# Round.net
KiCad netlist of a schematic drawn in EAGLE
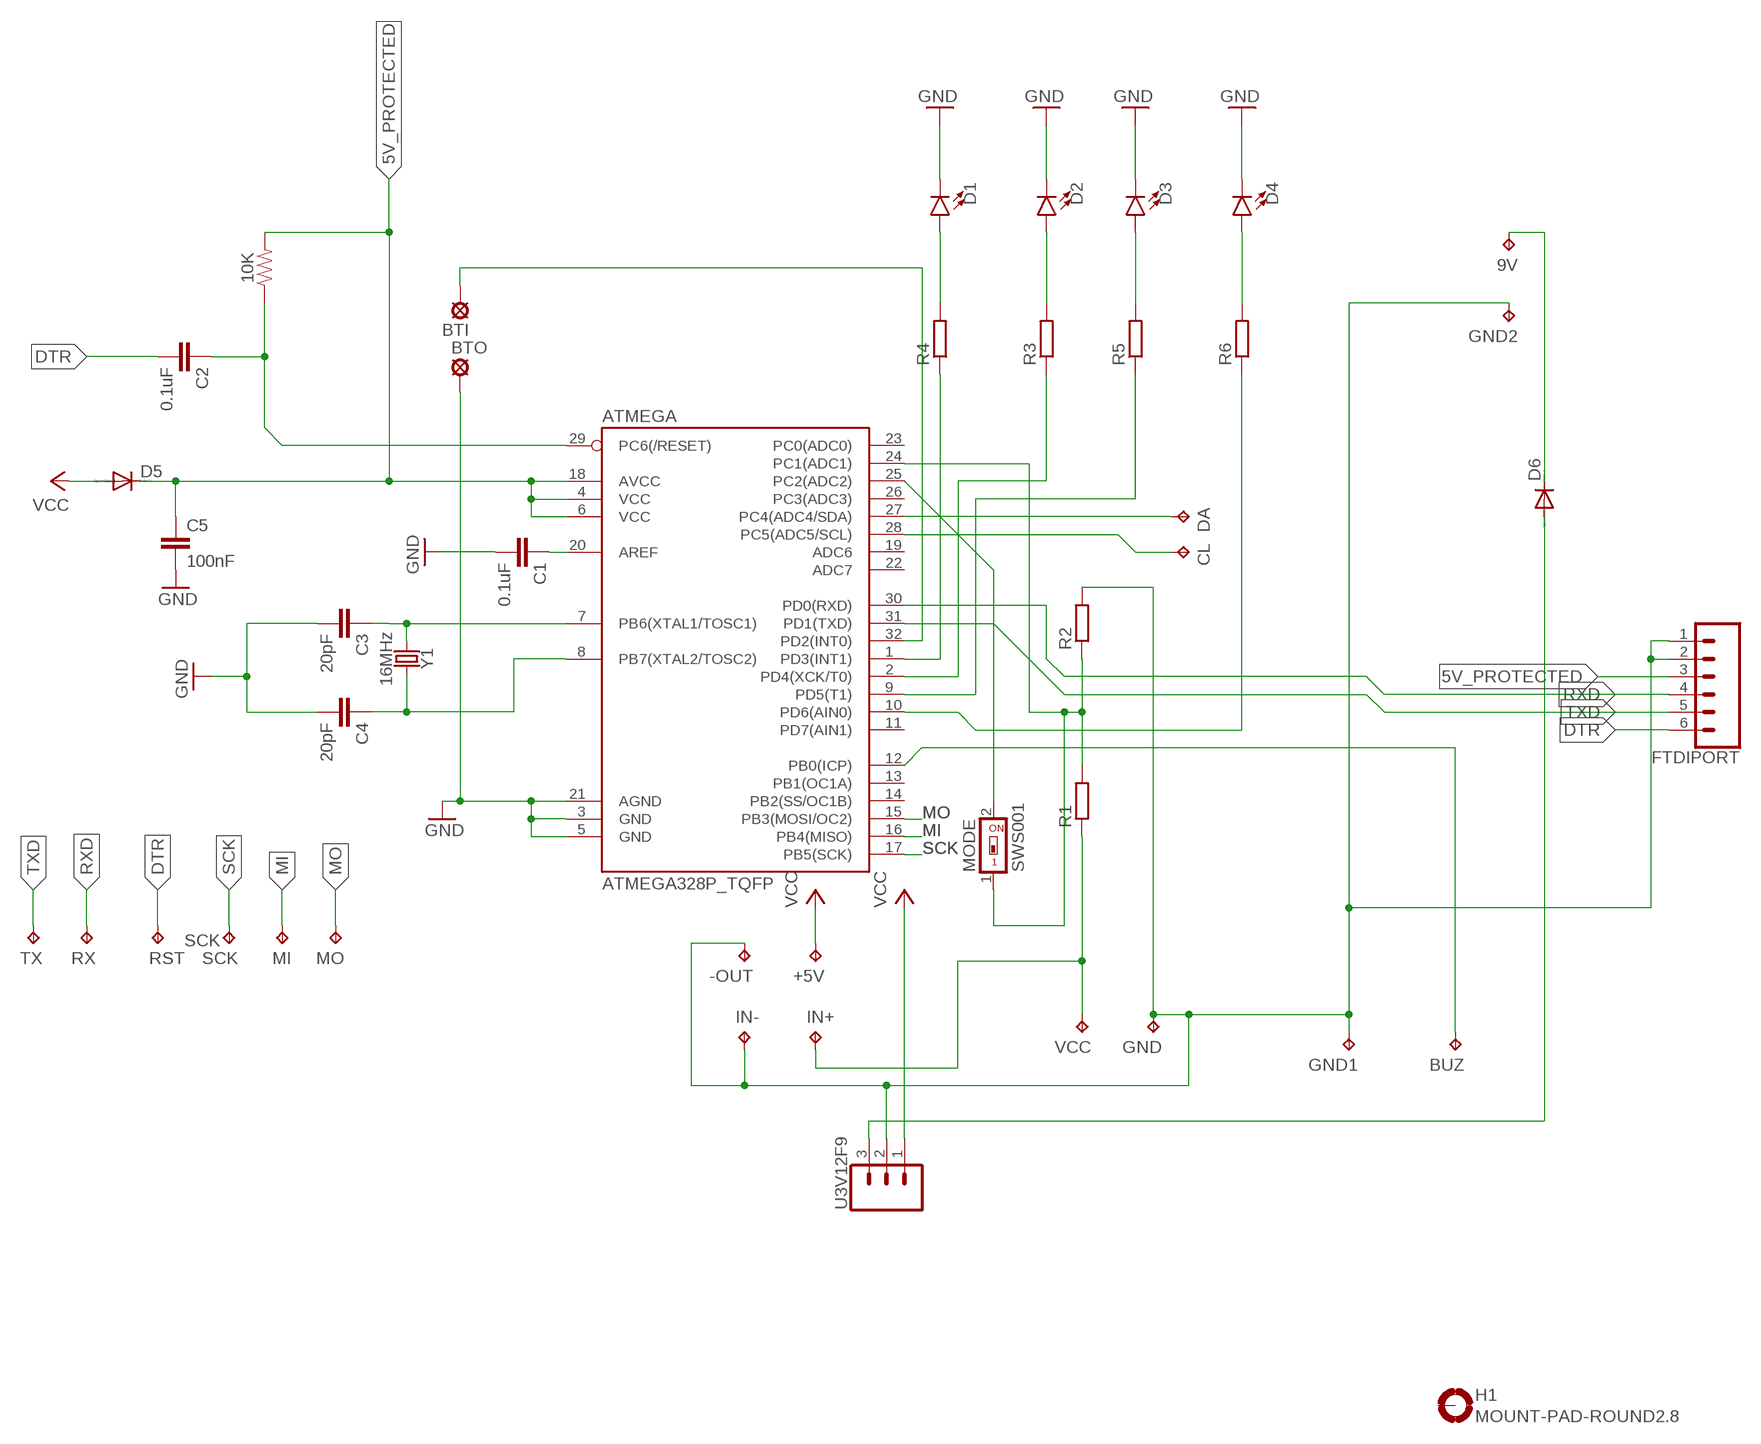
[diagram p0: schematic, sheet 1]

(export (version "E")
  (design (tool "Eeschema 10.0.6"))
  (components
    (comp (ref "+5V")
      (value "TPTP20SQ")
      (footprint "eagle-import:TP20SQ")
      (libsource (lib "eagle-import") (part "TPTP20SQ"))
    )
    (comp (ref "-OUT")
      (value "TPTP20SQ")
      (footprint "eagle-import:TP20SQ")
      (libsource (lib "eagle-import") (part "TPTP20SQ"))
    )
    (comp (ref "9V")
      (value "TPB2,54")
      (footprint "eagle-import:B2,54")
      (libsource (lib "eagle-import") (part "TPB2,54"))
    )
    (comp (ref "10K")
      (value "0.27OHM-0603-1/10W-1%")
      (footprint "eagle-import:0603")
      (libsource (lib "eagle-import") (part "0.27OHM-0603-1/10W-1%"))
    )
    (comp (ref "ATMEGA")
      (value "ATMEGA328P_TQFP")
      (footprint "eagle-import:TQFP32-08")
      (libsource (lib "eagle-import") (part "ATMEGA328P_TQFP"))
    )
    (comp (ref "BTI")
      (value "LSP10")
      (footprint "eagle-import:LSP10")
      (libsource (lib "eagle-import") (part "LSP10"))
    )
    (comp (ref "BTO")
      (value "LSP10")
      (footprint "eagle-import:LSP10")
      (libsource (lib "eagle-import") (part "LSP10"))
    )
    (comp (ref "BUZ")
      (value "TPB2,54")
      (footprint "eagle-import:B2,54")
      (libsource (lib "eagle-import") (part "TPB2,54"))
    )
    (comp (ref "C1")
      (value "0.1uF")
      (footprint "eagle-import:0603")
      (libsource (lib "eagle-import") (part "10NF-0603-50V-10%"))
    )
    (comp (ref "C2")
      (value "0.1uF")
      (footprint "eagle-import:0603")
      (libsource (lib "eagle-import") (part "10NF-0603-50V-10%"))
    )
    (comp (ref "C3")
      (value "20pF")
      (footprint "eagle-import:0603")
      (libsource (lib "eagle-import") (part "10NF-0603-50V-10%"))
    )
    (comp (ref "C4")
      (value "20pF")
      (footprint "eagle-import:0603")
      (libsource (lib "eagle-import") (part "10NF-0603-50V-10%"))
    )
    (comp (ref "C5")
      (value "100nF")
      (footprint "eagle-import:0603")
      (libsource (lib "eagle-import") (part "10NF-0603-50V-10%"))
    )
    (comp (ref "CL")
      (value "TPB1,27")
      (footprint "eagle-import:B1,27")
      (libsource (lib "eagle-import") (part "TPB1,27"))
    )
    (comp (ref "D1")
      (value "LED1206")
      (footprint "eagle-import:LED-1206")
      (libsource (lib "eagle-import") (part "LED1206"))
    )
    (comp (ref "D2")
      (value "LED1206")
      (footprint "eagle-import:LED-1206")
      (libsource (lib "eagle-import") (part "LED1206"))
    )
    (comp (ref "D3")
      (value "LED1206")
      (footprint "eagle-import:LED-1206")
      (libsource (lib "eagle-import") (part "LED1206"))
    )
    (comp (ref "D4")
      (value "LED1206")
      (footprint "eagle-import:LED-1206")
      (libsource (lib "eagle-import") (part "LED1206"))
    )
    (comp (ref "D5")
      (value "DIODE-SOD106A-R")
      (footprint "eagle-import:SOD106A-R")
      (libsource (lib "eagle-import") (part "DIODE-SOD106A-R"))
    )
    (comp (ref "D6")
      (value "DIODE-SOD106A-R")
      (footprint "eagle-import:SOD106A-R")
      (libsource (lib "eagle-import") (part "DIODE-SOD106A-R"))
    )
    (comp (ref "DA")
      (value "TPB1,27")
      (footprint "eagle-import:B1,27")
      (libsource (lib "eagle-import") (part "TPB1,27"))
    )
    (comp (ref "FTDIPORT")
      (value "CONN_06SMD-1MM")
      (footprint "eagle-import:1X06-1MM")
      (libsource (lib "eagle-import") (part "CONN_06SMD-1MM"))
    )
    (comp (ref "GND")
      (value "TPB2,54")
      (footprint "eagle-import:B2,54")
      (libsource (lib "eagle-import") (part "TPB2,54"))
    )
    (comp (ref "GND1")
      (value "TPB2,54")
      (footprint "eagle-import:B2,54")
      (libsource (lib "eagle-import") (part "TPB2,54"))
    )
    (comp (ref "GND2")
      (value "TPB2,54")
      (footprint "eagle-import:B2,54")
      (libsource (lib "eagle-import") (part "TPB2,54"))
    )
    (comp (ref "H1")
      (value "MOUNT-PAD-ROUND2.8")
      (footprint "eagle-import:2,8-PAD")
      (libsource (lib "eagle-import") (part "MOUNT-PAD-ROUND2.8"))
    )
    (comp (ref "IN+")
      (value "TPTP20SQ")
      (footprint "eagle-import:TP20SQ")
      (libsource (lib "eagle-import") (part "TPTP20SQ"))
    )
    (comp (ref "IN-")
      (value "TPTP20SQ")
      (footprint "eagle-import:TP20SQ")
      (libsource (lib "eagle-import") (part "TPTP20SQ"))
    )
    (comp (ref "MI")
      (value "TPB1,27")
      (footprint "eagle-import:B1,27")
      (libsource (lib "eagle-import") (part "TPB1,27"))
    )
    (comp (ref "MO")
      (value "TPB1,27")
      (footprint "eagle-import:B1,27")
      (libsource (lib "eagle-import") (part "TPB1,27"))
    )
    (comp (ref "MODE")
      (value "SWS001")
      (footprint "eagle-import:SMS-001")
      (libsource (lib "eagle-import") (part "SWS001"))
    )
    (comp (ref "R1")
      (value "R-EU_R1206")
      (footprint "eagle-import:R1206")
      (libsource (lib "eagle-import") (part "R-EU_R1206"))
    )
    (comp (ref "R2")
      (value "R-EU_R1206")
      (footprint "eagle-import:R1206")
      (libsource (lib "eagle-import") (part "R-EU_R1206"))
    )
    (comp (ref "R3")
      (value "R-EU_R1206")
      (footprint "eagle-import:R1206")
      (libsource (lib "eagle-import") (part "R-EU_R1206"))
    )
    (comp (ref "R4")
      (value "R-EU_R1206")
      (footprint "eagle-import:R1206")
      (libsource (lib "eagle-import") (part "R-EU_R1206"))
    )
    (comp (ref "R5")
      (value "R-EU_R1206")
      (footprint "eagle-import:R1206")
      (libsource (lib "eagle-import") (part "R-EU_R1206"))
    )
    (comp (ref "R6")
      (value "R-EU_R1206")
      (footprint "eagle-import:R1206")
      (libsource (lib "eagle-import") (part "R-EU_R1206"))
    )
    (comp (ref "RST")
      (value "TPB1,27")
      (footprint "eagle-import:B1,27")
      (libsource (lib "eagle-import") (part "TPB1,27"))
    )
    (comp (ref "RX")
      (value "TPB1,27")
      (footprint "eagle-import:B1,27")
      (libsource (lib "eagle-import") (part "TPB1,27"))
    )
    (comp (ref "SCK")
      (value "TPB1,27")
      (footprint "eagle-import:B1,27")
      (fields (field (name "TP_SIGNAL_NAME") "SCK"))
      (libsource (lib "eagle-import") (part "TPB1,27"))
    )
    (comp (ref "TX")
      (value "TPB1,27")
      (footprint "eagle-import:B1,27")
      (libsource (lib "eagle-import") (part "TPB1,27"))
    )
    (comp (ref "U3V12F9")
      (value "CONN_03")
      (footprint "eagle-import:1X03")
      (libsource (lib "eagle-import") (part "CONN_03"))
    )
    (comp (ref "VCC")
      (value "TPB2,54")
      (footprint "eagle-import:B2,54")
      (libsource (lib "eagle-import") (part "TPB2,54"))
    )
    (comp (ref "Y1")
      (value "16MHz")
      (footprint "eagle-import:CRYSTAL-SMD-5X3.2-2PAD")
      (libsource (lib "eagle-import") (part "CRYSTALSMD-5X3.2-2PAD"))
    )
  )
  (nets
    (net (code "1") (name "5V_PROTECTED") (class "Default")
      (node (ref "10K") (pin "2") (pinfunction "2_2") (pintype "passive"))
      (node (ref "ATMEGA") (pin "18") (pinfunction "AVCC_18") (pintype "bidirectional"))
      (node (ref "ATMEGA") (pin "4") (pinfunction "VCC_4") (pintype "bidirectional"))
      (node (ref "ATMEGA") (pin "6") (pinfunction "VCC_6") (pintype "bidirectional"))
      (node (ref "C5") (pin "1") (pinfunction "1_1") (pintype "passive"))
      (node (ref "D5") (pin "C") (pinfunction "C_C") (pintype "passive"))
      (node (ref "FTDIPORT") (pin "3") (pinfunction "3_3") (pintype "passive"))
    )
    (net (code "2") (name "DTR") (class "Default")
      (node (ref "C2") (pin "2") (pinfunction "2_2") (pintype "passive"))
      (node (ref "FTDIPORT") (pin "6") (pinfunction "6_6") (pintype "passive"))
      (node (ref "RST") (pin "TP") (pinfunction "TP_TP") (pintype "input"))
    )
    (net (code "3") (name "GND") (class "Default")
      (node (ref "-OUT") (pin "TP") (pinfunction "TP_TP") (pintype "input"))
      (node (ref "ATMEGA") (pin "21") (pinfunction "AGND_21") (pintype "bidirectional"))
      (node (ref "ATMEGA") (pin "3") (pinfunction "GND_3") (pintype "bidirectional"))
      (node (ref "ATMEGA") (pin "5") (pinfunction "GND_5") (pintype "bidirectional"))
      (node (ref "BTO") (pin "MP") (pinfunction "MP_MP") (pintype "passive"))
      (node (ref "C1") (pin "2") (pinfunction "2_2") (pintype "passive"))
      (node (ref "C3") (pin "2") (pinfunction "2_2") (pintype "passive"))
      (node (ref "C4") (pin "2") (pinfunction "2_2") (pintype "passive"))
      (node (ref "C5") (pin "2") (pinfunction "2_2") (pintype "passive"))
      (node (ref "D1") (pin "C") (pinfunction "C_C") (pintype "passive"))
      (node (ref "D2") (pin "C") (pinfunction "C_C") (pintype "passive"))
      (node (ref "D3") (pin "C") (pinfunction "C_C") (pintype "passive"))
      (node (ref "D4") (pin "C") (pinfunction "C_C") (pintype "passive"))
      (node (ref "FTDIPORT") (pin "1") (pinfunction "1_1") (pintype "passive"))
      (node (ref "FTDIPORT") (pin "2") (pinfunction "2_2") (pintype "passive"))
      (node (ref "GND") (pin "TP") (pinfunction "TP_TP") (pintype "input"))
      (node (ref "GND1") (pin "TP") (pinfunction "TP_TP") (pintype "input"))
      (node (ref "GND2") (pin "TP") (pinfunction "TP_TP") (pintype "input"))
      (node (ref "IN-") (pin "TP") (pinfunction "TP_TP") (pintype "input"))
      (node (ref "R2") (pin "2") (pinfunction "2_2") (pintype "passive"))
      (node (ref "U3V12F9") (pin "2") (pinfunction "2_2") (pintype "passive"))
    )
    (net (code "4") (name "MI") (class "Default")
      (node (ref "ATMEGA") (pin "16") (pinfunction "PB4(MISO)_16") (pintype "bidirectional"))
      (node (ref "MI") (pin "TP") (pinfunction "TP_TP") (pintype "input"))
    )
    (net (code "5") (name "MO") (class "Default")
      (node (ref "ATMEGA") (pin "15") (pinfunction "PB3(MOSI/OC2)_15") (pintype "bidirectional"))
      (node (ref "MO") (pin "TP") (pinfunction "TP_TP") (pintype "input"))
    )
    (net (code "6") (name "Net-(9V-PadTP)") (class "Default")
      (node (ref "9V") (pin "TP") (pinfunction "TP_TP") (pintype "input"))
      (node (ref "D6") (pin "C") (pinfunction "C_C") (pintype "passive"))
    )
    (net (code "7") (name "Net-(ATMEGA-AREF)") (class "Default")
      (node (ref "ATMEGA") (pin "20") (pinfunction "AREF_20") (pintype "bidirectional"))
      (node (ref "C1") (pin "1") (pinfunction "1_1") (pintype "passive"))
    )
    (net (code "8") (name "Net-(ATMEGA-PB0(ICP))") (class "Default")
      (node (ref "ATMEGA") (pin "12") (pinfunction "PB0(ICP)_12") (pintype "bidirectional"))
      (node (ref "BUZ") (pin "TP") (pinfunction "TP_TP") (pintype "input"))
    )
    (net (code "9") (name "Net-(ATMEGA-PB6(XTAL1{slash}TOSC1))") (class "Default")
      (node (ref "ATMEGA") (pin "7") (pinfunction "PB6(XTAL1/TOSC1)_7") (pintype "bidirectional"))
      (node (ref "C3") (pin "1") (pinfunction "1_1") (pintype "passive"))
      (node (ref "Y1") (pin "P$1") (pinfunction "1_P$1") (pintype "passive"))
    )
    (net (code "10") (name "Net-(ATMEGA-PB7(XTAL2{slash}TOSC2))") (class "Default")
      (node (ref "ATMEGA") (pin "8") (pinfunction "PB7(XTAL2/TOSC2)_8") (pintype "bidirectional"))
      (node (ref "C4") (pin "1") (pinfunction "1_1") (pintype "passive"))
      (node (ref "Y1") (pin "P$2") (pinfunction "2_P$2") (pintype "passive"))
    )
    (net (code "11") (name "Net-(ATMEGA-PC1(ADC1))") (class "Default")
      (node (ref "ATMEGA") (pin "24") (pinfunction "PC1(ADC1)_24") (pintype "bidirectional"))
      (node (ref "MODE") (pin "1") (pinfunction "1_1") (pintype "passive"))
      (node (ref "R1") (pin "2") (pinfunction "2_2") (pintype "passive"))
      (node (ref "R2") (pin "1") (pinfunction "1_1") (pintype "passive"))
    )
    (net (code "12") (name "Net-(ATMEGA-PC2(ADC2))") (class "Default")
      (node (ref "ATMEGA") (pin "25") (pinfunction "PC2(ADC2)_25") (pintype "bidirectional"))
      (node (ref "MODE") (pin "2") (pinfunction "2_2") (pintype "passive"))
    )
    (net (code "13") (name "Net-(ATMEGA-PC4(ADC4{slash}SDA))") (class "Default")
      (node (ref "ATMEGA") (pin "27") (pinfunction "PC4(ADC4/SDA)_27") (pintype "bidirectional"))
      (node (ref "DA") (pin "TP") (pinfunction "TP_TP") (pintype "input"))
    )
    (net (code "14") (name "Net-(ATMEGA-PC5(ADC5{slash}SCL))") (class "Default")
      (node (ref "ATMEGA") (pin "28") (pinfunction "PC5(ADC5/SCL)_28") (pintype "bidirectional"))
      (node (ref "CL") (pin "TP") (pinfunction "TP_TP") (pintype "input"))
    )
    (net (code "15") (name "Net-(ATMEGA-PC6({slash}RESET))") (class "Default")
      (node (ref "10K") (pin "1") (pinfunction "1_1") (pintype "passive"))
      (node (ref "ATMEGA") (pin "29") (pinfunction "PC6(/RESET)_29") (pintype "bidirectional"))
      (node (ref "C2") (pin "1") (pinfunction "1_1") (pintype "passive"))
    )
    (net (code "16") (name "Net-(ATMEGA-PD2(INT0))") (class "Default")
      (node (ref "ATMEGA") (pin "32") (pinfunction "PD2(INT0)_32") (pintype "bidirectional"))
      (node (ref "BTI") (pin "MP") (pinfunction "MP_MP") (pintype "passive"))
    )
    (net (code "17") (name "Net-(ATMEGA-PD3(INT1))") (class "Default")
      (node (ref "ATMEGA") (pin "1") (pinfunction "PD3(INT1)_1") (pintype "bidirectional"))
      (node (ref "R4") (pin "1") (pinfunction "1_1") (pintype "passive"))
    )
    (net (code "18") (name "Net-(ATMEGA-PD4(XCK{slash}T0))") (class "Default")
      (node (ref "ATMEGA") (pin "2") (pinfunction "PD4(XCK/T0)_2") (pintype "bidirectional"))
      (node (ref "R3") (pin "1") (pinfunction "1_1") (pintype "passive"))
    )
    (net (code "19") (name "Net-(ATMEGA-PD5(T1))") (class "Default")
      (node (ref "ATMEGA") (pin "9") (pinfunction "PD5(T1)_9") (pintype "bidirectional"))
      (node (ref "R5") (pin "1") (pinfunction "1_1") (pintype "passive"))
    )
    (net (code "20") (name "Net-(ATMEGA-PD6(AIN0))") (class "Default")
      (node (ref "ATMEGA") (pin "10") (pinfunction "PD6(AIN0)_10") (pintype "bidirectional"))
      (node (ref "R6") (pin "1") (pinfunction "1_1") (pintype "passive"))
    )
    (net (code "21") (name "Net-(D1-PadA)") (class "Default")
      (node (ref "D1") (pin "A") (pinfunction "A_A") (pintype "passive"))
      (node (ref "R4") (pin "2") (pinfunction "2_2") (pintype "passive"))
    )
    (net (code "22") (name "Net-(D2-PadA)") (class "Default")
      (node (ref "D2") (pin "A") (pinfunction "A_A") (pintype "passive"))
      (node (ref "R3") (pin "2") (pinfunction "2_2") (pintype "passive"))
    )
    (net (code "23") (name "Net-(D3-PadA)") (class "Default")
      (node (ref "D3") (pin "A") (pinfunction "A_A") (pintype "passive"))
      (node (ref "R5") (pin "2") (pinfunction "2_2") (pintype "passive"))
    )
    (net (code "24") (name "Net-(D4-PadA)") (class "Default")
      (node (ref "D4") (pin "A") (pinfunction "A_A") (pintype "passive"))
      (node (ref "R6") (pin "2") (pinfunction "2_2") (pintype "passive"))
    )
    (net (code "25") (name "Net-(D6-PadA)") (class "Default")
      (node (ref "D6") (pin "A") (pinfunction "A_A") (pintype "passive"))
      (node (ref "U3V12F9") (pin "3") (pinfunction "3_3") (pintype "passive"))
    )
    (net (code "26") (name "RXD") (class "Default")
      (node (ref "ATMEGA") (pin "30") (pinfunction "PD0(RXD)_30") (pintype "bidirectional"))
      (node (ref "FTDIPORT") (pin "4") (pinfunction "4_4") (pintype "passive"))
      (node (ref "RX") (pin "TP") (pinfunction "TP_TP") (pintype "input"))
    )
    (net (code "27") (name "SCK") (class "Default")
      (node (ref "ATMEGA") (pin "17") (pinfunction "PB5(SCK)_17") (pintype "bidirectional"))
      (node (ref "SCK") (pin "TP") (pinfunction "TP_TP") (pintype "input"))
    )
    (net (code "28") (name "TXD") (class "Default")
      (node (ref "ATMEGA") (pin "31") (pinfunction "PD1(TXD)_31") (pintype "bidirectional"))
      (node (ref "FTDIPORT") (pin "5") (pinfunction "5_5") (pintype "passive"))
      (node (ref "TX") (pin "TP") (pinfunction "TP_TP") (pintype "input"))
    )
    (net (code "29") (name "VCC") (class "Default")
      (node (ref "+5V") (pin "TP") (pinfunction "TP_TP") (pintype "input"))
      (node (ref "D5") (pin "A") (pinfunction "A_A") (pintype "passive"))
      (node (ref "IN+") (pin "TP") (pinfunction "TP_TP") (pintype "input"))
      (node (ref "R1") (pin "1") (pinfunction "1_1") (pintype "passive"))
      (node (ref "U3V12F9") (pin "1") (pinfunction "1_1") (pintype "passive"))
      (node (ref "VCC") (pin "TP") (pinfunction "TP_TP") (pintype "input"))
    )
    (net (code "30") (name "unconnected-(ATMEGA-ADC6-Pad19)") (class "Default")
      (node (ref "ATMEGA") (pin "19") (pinfunction "ADC6_19") (pintype "bidirectional"))
    )
    (net (code "31") (name "unconnected-(ATMEGA-ADC7-Pad22)") (class "Default")
      (node (ref "ATMEGA") (pin "22") (pinfunction "ADC7_22") (pintype "bidirectional"))
    )
    (net (code "32") (name "unconnected-(ATMEGA-PB1(OC1A)-Pad13)") (class "Default")
      (node (ref "ATMEGA") (pin "13") (pinfunction "PB1(OC1A)_13") (pintype "bidirectional"))
    )
    (net (code "33") (name "unconnected-(ATMEGA-PB2(SS{slash}OC1B)-Pad14)") (class "Default")
      (node (ref "ATMEGA") (pin "14") (pinfunction "PB2(SS/OC1B)_14") (pintype "bidirectional"))
    )
    (net (code "34") (name "unconnected-(ATMEGA-PC0(ADC0)-Pad23)") (class "Default")
      (node (ref "ATMEGA") (pin "23") (pinfunction "PC0(ADC0)_23") (pintype "bidirectional"))
    )
    (net (code "35") (name "unconnected-(ATMEGA-PC3(ADC3)-Pad26)") (class "Default")
      (node (ref "ATMEGA") (pin "26") (pinfunction "PC3(ADC3)_26") (pintype "bidirectional"))
    )
    (net (code "36") (name "unconnected-(ATMEGA-PD7(AIN1)-Pad11)") (class "Default")
      (node (ref "ATMEGA") (pin "11") (pinfunction "PD7(AIN1)_11") (pintype "bidirectional"))
    )
    (net (code "37") (name "unconnected-(H1-MOUNT-PadB2,8)") (class "Default")
      (node (ref "H1") (pin "B2,8") (pinfunction "MOUNT_B2,8") (pintype "passive"))
    )
  )
)
